# OSDK_USB-C-3.net
KiCad netlist of a schematic drawn in EAGLE
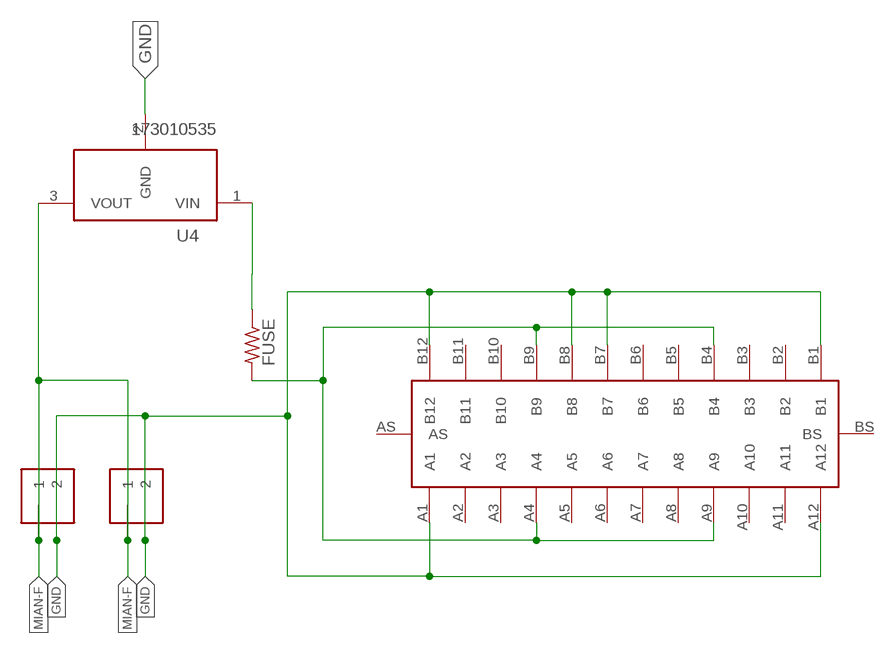
[diagram p0: schematic, sheet 1]

(export (version "E")
  (design (tool "Eeschema 10.0.6"))
  (components
    (comp (ref "CU3124PAAHLA002-NH")
      (value "USB-C")
      (footprint "eagle-import:USB-C")
      (libsource (lib "eagle-import") (part "USB-C"))
    )
    (comp (ref "FUSE")
      (value "R-US_0207/9")
      (footprint "eagle-import:0207_9")
      (libsource (lib "eagle-import") (part "R-US_0207/9"))
    )
    (comp (ref "J1")
      (value "ADAFRUIT_1X2-3.5MM")
      (footprint "eagle-import:ADAFRUIT_1X2-3.5MM")
      (libsource (lib "eagle-import") (part "ADAFRUIT_1X2-3.5MM"))
    )
    (comp (ref "J2")
      (value "ADAFRUIT_1X2-3.5MM")
      (footprint "eagle-import:ADAFRUIT_1X2-3.5MM")
      (libsource (lib "eagle-import") (part "ADAFRUIT_1X2-3.5MM"))
    )
    (comp (ref "U4")
      (value "173010535")
      (footprint "eagle-import:173010535")
      (fields
        (field (name "DIGIKEY_PARTNO") "732-173010535-ND")
        (field (name "MANUFACTURER") "Würth Elektronik")
        (field (name "CREATED_BY") "PCBLayout.com")
      )
      (libsource (lib "eagle-import") (part "173010535"))
    )
  )
  (nets
    (net (code "1") (name "GND") (class "Default")
      (node (ref "CU3124PAAHLA002-NH") (pin "A1") (pinfunction "A1_A1") (pintype "bidirectional"))
      (node (ref "CU3124PAAHLA002-NH") (pin "A12") (pinfunction "A12_A12") (pintype "bidirectional"))
      (node (ref "CU3124PAAHLA002-NH") (pin "B1") (pinfunction "B1_B1") (pintype "bidirectional"))
      (node (ref "CU3124PAAHLA002-NH") (pin "B12") (pinfunction "B12_B12") (pintype "bidirectional"))
      (node (ref "CU3124PAAHLA002-NH") (pin "B7") (pinfunction "B7_B7") (pintype "bidirectional"))
      (node (ref "CU3124PAAHLA002-NH") (pin "B8") (pinfunction "B8_B8") (pintype "bidirectional"))
      (node (ref "J1") (pin "2") (pinfunction "2_2") (pintype "passive"))
      (node (ref "J2") (pin "2") (pinfunction "2_2") (pintype "passive"))
      (node (ref "U4") (pin "2") (pinfunction "GND_2") (pintype "power_in"))
    )
    (net (code "2") (name "MIAN-F") (class "Default")
      (node (ref "J1") (pin "1") (pinfunction "1_1") (pintype "passive"))
      (node (ref "J2") (pin "1") (pinfunction "1_1") (pintype "passive"))
      (node (ref "U4") (pin "3") (pinfunction "VOUT_3") (pintype "power_in"))
    )
    (net (code "3") (name "Net-(CU3124PAAHLA002-NH-PadA4)") (class "Default")
      (node (ref "CU3124PAAHLA002-NH") (pin "A4") (pinfunction "A4_A4") (pintype "bidirectional"))
      (node (ref "CU3124PAAHLA002-NH") (pin "A9") (pinfunction "A9_A9") (pintype "bidirectional"))
      (node (ref "CU3124PAAHLA002-NH") (pin "B4") (pinfunction "B4_B4") (pintype "bidirectional"))
      (node (ref "CU3124PAAHLA002-NH") (pin "B9") (pinfunction "B9_B9") (pintype "bidirectional"))
      (node (ref "FUSE") (pin "2") (pinfunction "2_2") (pintype "passive"))
    )
    (net (code "4") (name "Net-(U4-VIN)") (class "Default")
      (node (ref "FUSE") (pin "1") (pinfunction "1_1") (pintype "passive"))
      (node (ref "U4") (pin "1") (pinfunction "VIN_1") (pintype "power_in"))
    )
    (net (code "5") (name "unconnected-(CU3124PAAHLA002-NH-PadA2)") (class "Default")
      (node (ref "CU3124PAAHLA002-NH") (pin "A2") (pinfunction "A2_A2") (pintype "bidirectional"))
    )
    (net (code "6") (name "unconnected-(CU3124PAAHLA002-NH-PadA3)") (class "Default")
      (node (ref "CU3124PAAHLA002-NH") (pin "A3") (pinfunction "A3_A3") (pintype "bidirectional"))
    )
    (net (code "7") (name "unconnected-(CU3124PAAHLA002-NH-PadA5)") (class "Default")
      (node (ref "CU3124PAAHLA002-NH") (pin "A5") (pinfunction "A5_A5") (pintype "bidirectional"))
    )
    (net (code "8") (name "unconnected-(CU3124PAAHLA002-NH-PadA6)") (class "Default")
      (node (ref "CU3124PAAHLA002-NH") (pin "A6") (pinfunction "A6_A6") (pintype "bidirectional"))
    )
    (net (code "9") (name "unconnected-(CU3124PAAHLA002-NH-PadA7)") (class "Default")
      (node (ref "CU3124PAAHLA002-NH") (pin "A7") (pinfunction "A7_A7") (pintype "bidirectional"))
    )
    (net (code "10") (name "unconnected-(CU3124PAAHLA002-NH-PadA8)") (class "Default")
      (node (ref "CU3124PAAHLA002-NH") (pin "A8") (pinfunction "A8_A8") (pintype "bidirectional"))
    )
    (net (code "11") (name "unconnected-(CU3124PAAHLA002-NH-PadA10)") (class "Default")
      (node (ref "CU3124PAAHLA002-NH") (pin "A10") (pinfunction "A10_A10") (pintype "bidirectional"))
    )
    (net (code "12") (name "unconnected-(CU3124PAAHLA002-NH-PadA11)") (class "Default")
      (node (ref "CU3124PAAHLA002-NH") (pin "A11") (pinfunction "A11_A11") (pintype "bidirectional"))
    )
    (net (code "13") (name "unconnected-(CU3124PAAHLA002-NH-PadAS)") (class "Default")
      (node (ref "CU3124PAAHLA002-NH") (pin "AS") (pinfunction "AS_AS") (pintype "bidirectional"))
    )
    (net (code "14") (name "unconnected-(CU3124PAAHLA002-NH-PadB2)") (class "Default")
      (node (ref "CU3124PAAHLA002-NH") (pin "B2") (pinfunction "B2_B2") (pintype "bidirectional"))
    )
    (net (code "15") (name "unconnected-(CU3124PAAHLA002-NH-PadB3)") (class "Default")
      (node (ref "CU3124PAAHLA002-NH") (pin "B3") (pinfunction "B3_B3") (pintype "bidirectional"))
    )
    (net (code "16") (name "unconnected-(CU3124PAAHLA002-NH-PadB5)") (class "Default")
      (node (ref "CU3124PAAHLA002-NH") (pin "B5") (pinfunction "B5_B5") (pintype "bidirectional"))
    )
    (net (code "17") (name "unconnected-(CU3124PAAHLA002-NH-PadB6)") (class "Default")
      (node (ref "CU3124PAAHLA002-NH") (pin "B6") (pinfunction "B6_B6") (pintype "bidirectional"))
    )
    (net (code "18") (name "unconnected-(CU3124PAAHLA002-NH-PadB10)") (class "Default")
      (node (ref "CU3124PAAHLA002-NH") (pin "B10") (pinfunction "B10_B10") (pintype "bidirectional"))
    )
    (net (code "19") (name "unconnected-(CU3124PAAHLA002-NH-PadB11)") (class "Default")
      (node (ref "CU3124PAAHLA002-NH") (pin "B11") (pinfunction "B11_B11") (pintype "bidirectional"))
    )
    (net (code "20") (name "unconnected-(CU3124PAAHLA002-NH-PadBS)") (class "Default")
      (node (ref "CU3124PAAHLA002-NH") (pin "BS") (pinfunction "BS_BS") (pintype "bidirectional"))
    )
  )
)
